# tejesh.net
KiCad netlist of a schematic drawn in EAGLE
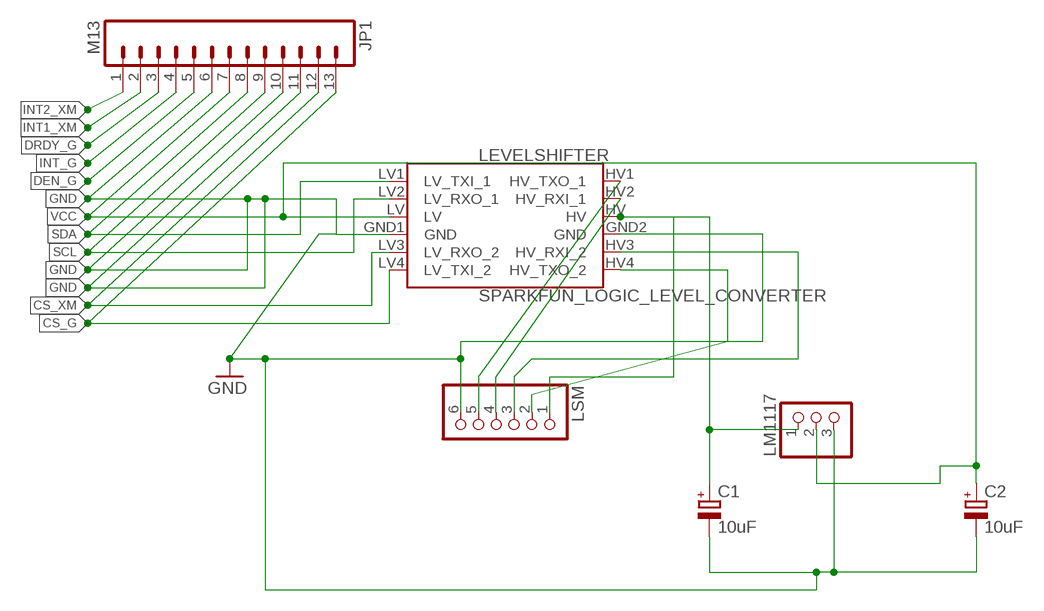
[diagram p0: schematic, sheet 1]

(export (version "E")
  (design (tool "Eeschema 10.0.6"))
  (components
    (comp (ref "C1")
      (value "10uF")
      (footprint "eagle-import:E2,5-6")
      (libsource (lib "eagle-import") (part "CPOL-EUE2.5-6"))
    )
    (comp (ref "C2")
      (value "10uF")
      (footprint "eagle-import:E2,5-6")
      (libsource (lib "eagle-import") (part "CPOL-EUE2.5-6"))
    )
    (comp (ref "JP1")
      (value "M13")
      (footprint "eagle-import:1X13")
      (libsource (lib "eagle-import") (part "M13"))
    )
    (comp (ref "LEVELSHIFTER")
      (value "SPARKFUN_LOGIC_LEVEL_CONVERTER")
      (footprint "eagle-import:SPARKFUN_LOGIC_LEVEL_CONVERTER")
      (libsource (lib "eagle-import") (part "SPARKFUN_LOGIC_LEVEL_CONVERTER"))
    )
    (comp (ref "LM1117")
      (value "PINHD-1X3")
      (footprint "eagle-import:1X03")
      (libsource (lib "eagle-import") (part "PINHD-1X3"))
    )
    (comp (ref "LSM")
      (value "PINHD-1X6")
      (footprint "eagle-import:1X06")
      (libsource (lib "eagle-import") (part "PINHD-1X6"))
    )
  )
  (nets
    (net (code "1") (name "CS_G") (class "Default")
      (node (ref "JP1") (pin "13") (pinfunction "13_13") (pintype "passive"))
      (node (ref "LEVELSHIFTER") (pin "LV4") (pinfunction "LV_TXI_2_LV4") (pintype "bidirectional"))
    )
    (net (code "2") (name "CS_XM") (class "Default")
      (node (ref "JP1") (pin "12") (pinfunction "12_12") (pintype "passive"))
      (node (ref "LEVELSHIFTER") (pin "LV3") (pinfunction "LV_RXO_2_LV3") (pintype "bidirectional"))
    )
    (net (code "3") (name "DEN_G") (class "Default")
      (node (ref "JP1") (pin "5") (pinfunction "5_5") (pintype "passive"))
    )
    (net (code "4") (name "DRDY_G") (class "Default")
      (node (ref "JP1") (pin "3") (pinfunction "3_3") (pintype "passive"))
    )
    (net (code "5") (name "GND") (class "Default")
      (node (ref "C1") (pin "-") (pinfunction "-_-") (pintype "passive"))
      (node (ref "C2") (pin "-") (pinfunction "-_-") (pintype "passive"))
      (node (ref "JP1") (pin "10") (pinfunction "10_10") (pintype "passive"))
      (node (ref "JP1") (pin "11") (pinfunction "11_11") (pintype "passive"))
      (node (ref "JP1") (pin "6") (pinfunction "6_6") (pintype "passive"))
      (node (ref "LEVELSHIFTER") (pin "GND1") (pinfunction "GND_GND1") (pintype "power_in"))
      (node (ref "LEVELSHIFTER") (pin "GND2") (pinfunction "GND_GND2") (pintype "power_in"))
      (node (ref "LM1117") (pin "3") (pinfunction "3_3") (pintype "passive"))
      (node (ref "LSM") (pin "6") (pinfunction "6_6") (pintype "passive"))
    )
    (net (code "6") (name "INT1_XM") (class "Default")
      (node (ref "JP1") (pin "2") (pinfunction "2_2") (pintype "passive"))
    )
    (net (code "7") (name "INT2_XM") (class "Default")
      (node (ref "JP1") (pin "1") (pinfunction "1_1") (pintype "passive"))
    )
    (net (code "8") (name "INT_G") (class "Default")
      (node (ref "JP1") (pin "4") (pinfunction "4_4") (pintype "passive"))
    )
    (net (code "9") (name "Net-(C1-Pad+)") (class "Default")
      (node (ref "C1") (pin "+") (pinfunction "+_+") (pintype "passive"))
      (node (ref "LEVELSHIFTER") (pin "HV") (pinfunction "HV_HV") (pintype "power_in"))
      (node (ref "LM1117") (pin "1") (pinfunction "1_1") (pintype "passive"))
      (node (ref "LSM") (pin "1") (pinfunction "1_1") (pintype "passive"))
    )
    (net (code "10") (name "Net-(LEVELSHIFTER-HV_RXI_1)") (class "Default")
      (node (ref "LEVELSHIFTER") (pin "HV2") (pinfunction "HV_RXI_1_HV2") (pintype "bidirectional"))
      (node (ref "LSM") (pin "4") (pinfunction "4_4") (pintype "passive"))
    )
    (net (code "11") (name "Net-(LEVELSHIFTER-HV_RXI_2)") (class "Default")
      (node (ref "LEVELSHIFTER") (pin "HV3") (pinfunction "HV_RXI_2_HV3") (pintype "bidirectional"))
      (node (ref "LSM") (pin "3") (pinfunction "3_3") (pintype "passive"))
    )
    (net (code "12") (name "Net-(LEVELSHIFTER-HV_TXO_1)") (class "Default")
      (node (ref "LEVELSHIFTER") (pin "HV1") (pinfunction "HV_TXO_1_HV1") (pintype "bidirectional"))
      (node (ref "LSM") (pin "5") (pinfunction "5_5") (pintype "passive"))
    )
    (net (code "13") (name "Net-(LEVELSHIFTER-HV_TXO_2)") (class "Default")
      (node (ref "LEVELSHIFTER") (pin "HV4") (pinfunction "HV_TXO_2_HV4") (pintype "bidirectional"))
      (node (ref "LSM") (pin "2") (pinfunction "2_2") (pintype "passive"))
    )
    (net (code "14") (name "SCL") (class "Default")
      (node (ref "JP1") (pin "9") (pinfunction "9_9") (pintype "passive"))
      (node (ref "LEVELSHIFTER") (pin "LV2") (pinfunction "LV_RXO_1_LV2") (pintype "bidirectional"))
    )
    (net (code "15") (name "SDA") (class "Default")
      (node (ref "JP1") (pin "8") (pinfunction "8_8") (pintype "passive"))
      (node (ref "LEVELSHIFTER") (pin "LV1") (pinfunction "LV_TXI_1_LV1") (pintype "bidirectional"))
    )
    (net (code "16") (name "VCC") (class "Default")
      (node (ref "C2") (pin "+") (pinfunction "+_+") (pintype "passive"))
      (node (ref "JP1") (pin "7") (pinfunction "7_7") (pintype "passive"))
      (node (ref "LEVELSHIFTER") (pin "LV") (pinfunction "LV_LV") (pintype "power_in"))
      (node (ref "LM1117") (pin "2") (pinfunction "2_2") (pintype "passive"))
    )
  )
)
